# Moirai.net
KiCad netlist of a schematic drawn in EAGLE
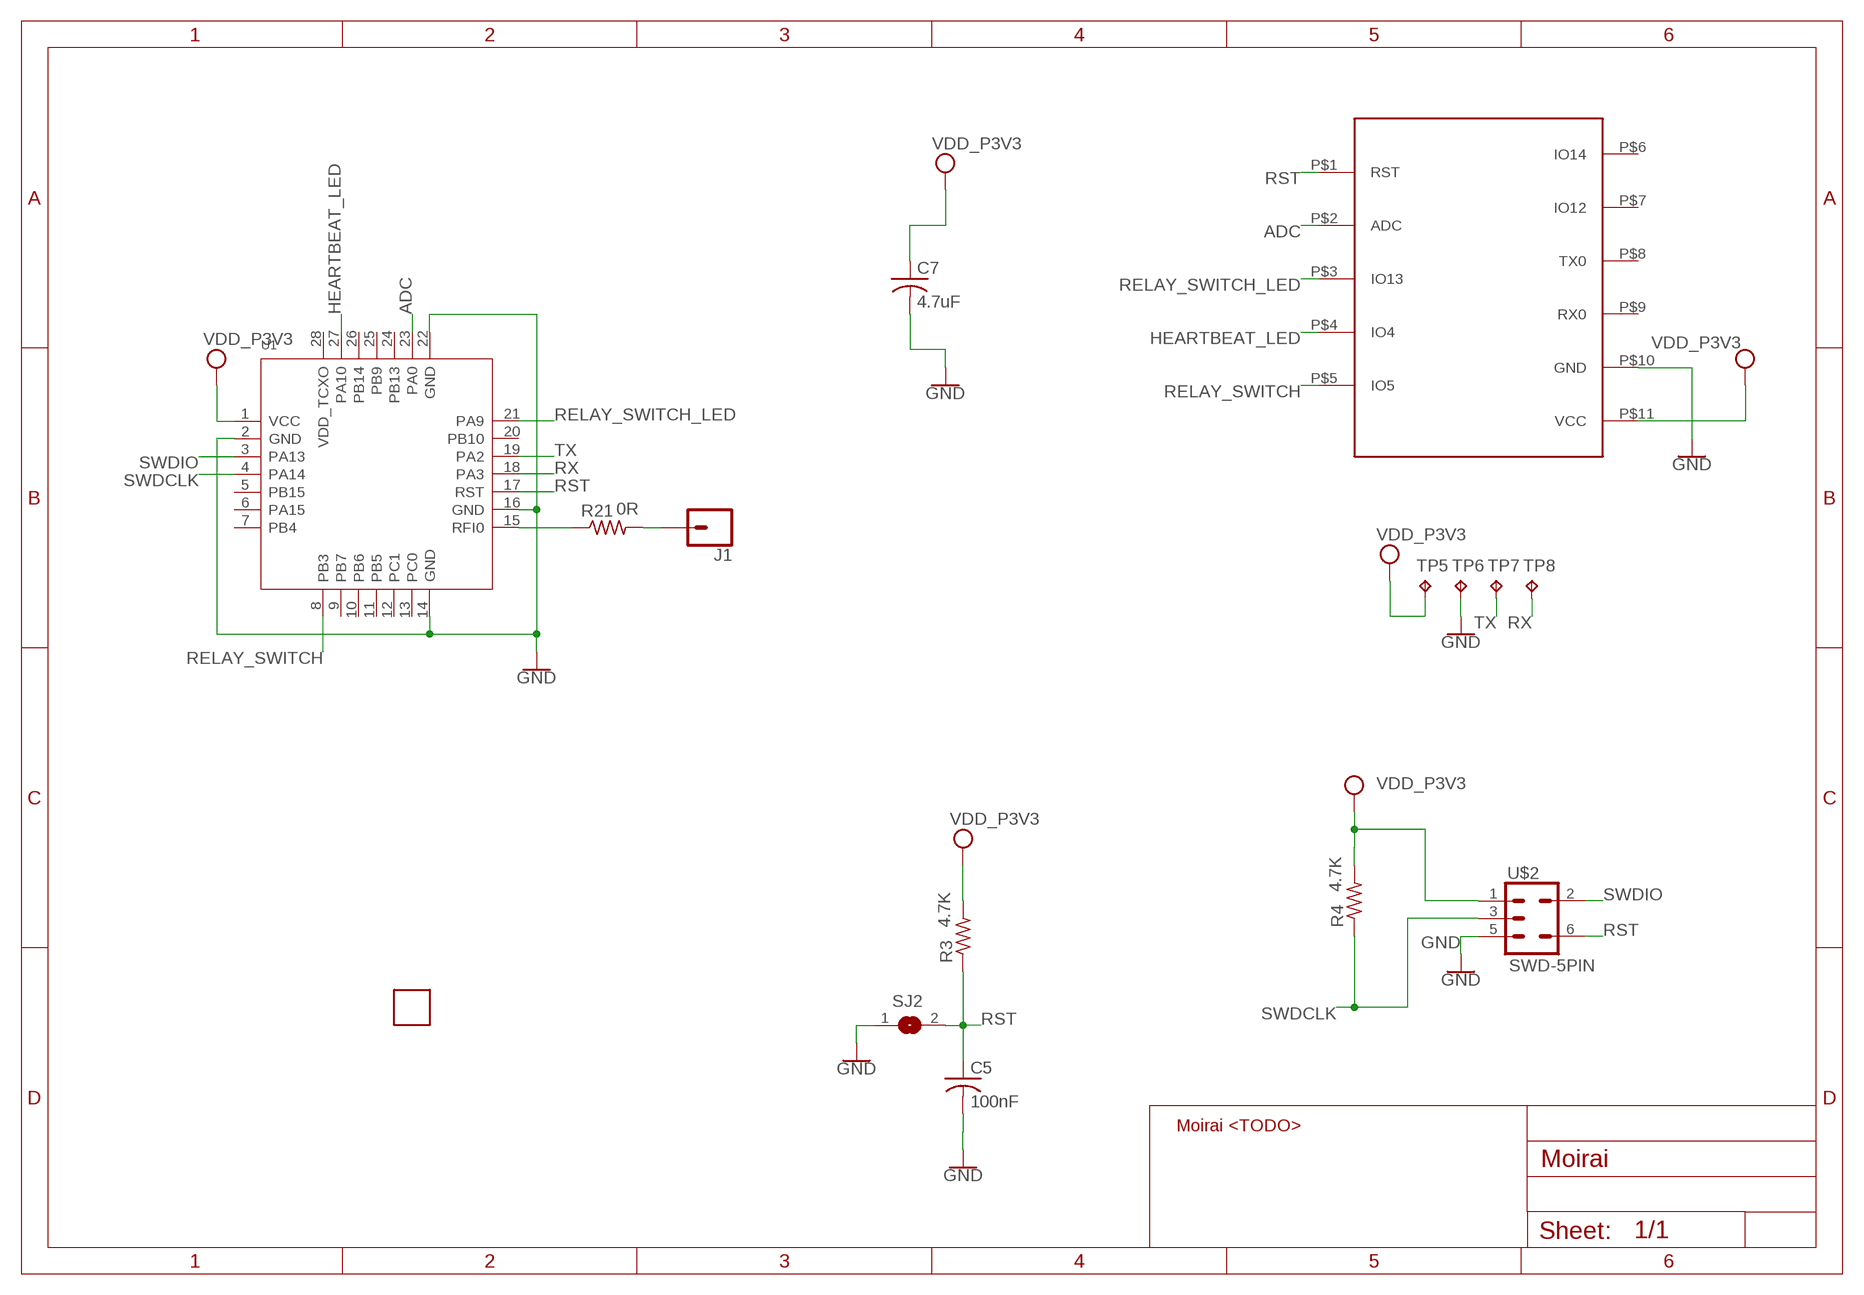
[diagram p0: schematic, sheet 1]

(export (version "E")
  (design (tool "Eeschema 10.0.6"))
  (components
    (comp (ref "C5")
      (value "100nF")
      (footprint "eagle-import:C0402")
      (libsource (lib "eagle-import") (part "C-USC0402"))
    )
    (comp (ref "C7")
      (value "4.7uF")
      (footprint "eagle-import:C0402")
      (libsource (lib "eagle-import") (part "C-USC0402"))
    )
    (comp (ref "J1")
      (value "CONN_01")
      (footprint "eagle-import:1X01")
      (libsource (lib "eagle-import") (part "CONN_01"))
    )
    (comp (ref "R3")
      (value "4.7K")
      (footprint "eagle-import:R0402")
      (libsource (lib "eagle-import") (part "R-US_R0402"))
    )
    (comp (ref "R4")
      (value "4.7K")
      (footprint "eagle-import:R0402")
      (libsource (lib "eagle-import") (part "R-US_R0402"))
    )
    (comp (ref "R21")
      (value "0R")
      (footprint "eagle-import:R0402")
      (libsource (lib "eagle-import") (part "R-US_R0402"))
    )
    (comp (ref "SJ2") (value "SJ") (footprint "eagle-import:SJ") (libsource (lib "eagle-import") (part "SJ")))
    (comp (ref "TP5")
      (value "TPB1,27")
      (footprint "eagle-import:B1,27")
      (libsource (lib "eagle-import") (part "TPB1,27"))
    )
    (comp (ref "TP6")
      (value "TPB1,27")
      (footprint "eagle-import:B1,27")
      (libsource (lib "eagle-import") (part "TPB1,27"))
    )
    (comp (ref "TP7")
      (value "TPB1,27")
      (footprint "eagle-import:B1,27")
      (libsource (lib "eagle-import") (part "TPB1,27"))
    )
    (comp (ref "TP8")
      (value "TPB1,27")
      (footprint "eagle-import:B1,27")
      (libsource (lib "eagle-import") (part "TPB1,27"))
    )
    (comp (ref "U$1")
      (value "ESP02SESP02S_MIRROR")
      (footprint "eagle-import:ESP02S_MIRROR")
      (libsource (lib "eagle-import") (part "ESP02SESP02S_MIRROR"))
    )
    (comp (ref "U$2")
      (value "SWD-5PIN")
      (footprint "eagle-import:PAD_05_03X2_TP_NO4")
      (libsource (lib "eagle-import") (part "SWD-5PIN"))
    )
    (comp (ref "U$3")
      (value "SMARTT_SMALL")
      (footprint "eagle-import:SMARTT_SMALL")
      (libsource (lib "eagle-import") (part "SMARTT_SMALL"))
    )
    (comp (ref "U1")
      (value "MODULE_LORA_E5")
      (footprint "eagle-import:MODULE28P-1.25-12X12X2.5MM")
      (libsource (lib "eagle-import") (part "MODULE_LORA_E5"))
    )
  )
  (nets
    (net (code "1") (name "/ADC") (class "Default")
      (node (ref "U$1") (pin "P$2") (pinfunction "ADC_P$2") (pintype "input"))
      (node (ref "U1") (pin "23") (pinfunction "PA0_23") (pintype "bidirectional"))
    )
    (net (code "2") (name "/HEARTBEAT_LED") (class "Default")
      (node (ref "U$1") (pin "P$4") (pinfunction "IO4_P$4") (pintype "bidirectional"))
      (node (ref "U1") (pin "27") (pinfunction "PA10_27") (pintype "bidirectional"))
    )
    (net (code "3") (name "/RELAY_SWITCH") (class "Default")
      (node (ref "U$1") (pin "P$5") (pinfunction "IO5_P$5") (pintype "bidirectional"))
      (node (ref "U1") (pin "8") (pinfunction "PB3_8") (pintype "bidirectional"))
    )
    (net (code "4") (name "/RELAY_SWITCH_LED") (class "Default")
      (node (ref "U$1") (pin "P$3") (pinfunction "IO13_P$3") (pintype "bidirectional"))
      (node (ref "U1") (pin "21") (pinfunction "PA9_21") (pintype "bidirectional"))
    )
    (net (code "5") (name "/RST") (class "Default")
      (node (ref "C5") (pin "1") (pinfunction "1_1") (pintype "passive"))
      (node (ref "R3") (pin "1") (pinfunction "1_1") (pintype "passive"))
      (node (ref "SJ2") (pin "2") (pinfunction "2_2") (pintype "passive"))
      (node (ref "U$1") (pin "P$1") (pinfunction "RST_P$1") (pintype "input"))
      (node (ref "U$2") (pin "6") (pinfunction "6_6") (pintype "bidirectional"))
      (node (ref "U1") (pin "17") (pinfunction "RST_17") (pintype "bidirectional"))
    )
    (net (code "6") (name "/RX") (class "Default")
      (node (ref "TP8") (pin "TP") (pinfunction "TP_TP") (pintype "input"))
      (node (ref "U1") (pin "18") (pinfunction "PA3_18") (pintype "bidirectional"))
    )
    (net (code "7") (name "/SWDCLK") (class "Default")
      (node (ref "R4") (pin "1") (pinfunction "1_1") (pintype "passive"))
      (node (ref "U$2") (pin "3") (pinfunction "3_3") (pintype "bidirectional"))
      (node (ref "U1") (pin "4") (pinfunction "PA14_4") (pintype "bidirectional"))
    )
    (net (code "8") (name "/SWDIO") (class "Default")
      (node (ref "U$2") (pin "2") (pinfunction "2_2") (pintype "bidirectional"))
      (node (ref "U1") (pin "3") (pinfunction "PA13_3") (pintype "bidirectional"))
    )
    (net (code "9") (name "/TX") (class "Default")
      (node (ref "TP7") (pin "TP") (pinfunction "TP_TP") (pintype "input"))
      (node (ref "U1") (pin "19") (pinfunction "PA2_19") (pintype "bidirectional"))
    )
    (net (code "10") (name "GND") (class "Default")
      (node (ref "C5") (pin "2") (pinfunction "2_2") (pintype "passive"))
      (node (ref "C7") (pin "2") (pinfunction "2_2") (pintype "passive"))
      (node (ref "SJ2") (pin "1") (pinfunction "1_1") (pintype "passive"))
      (node (ref "TP6") (pin "TP") (pinfunction "TP_TP") (pintype "input"))
      (node (ref "U$1") (pin "P$10") (pinfunction "GND_P$10") (pintype "power_in"))
      (node (ref "U$2") (pin "5") (pinfunction "5_5") (pintype "bidirectional"))
      (node (ref "U1") (pin "14") (pinfunction "GND_14") (pintype "bidirectional"))
      (node (ref "U1") (pin "16") (pinfunction "GND_16") (pintype "bidirectional"))
      (node (ref "U1") (pin "2") (pinfunction "GND_2") (pintype "bidirectional"))
      (node (ref "U1") (pin "22") (pinfunction "GND_22") (pintype "bidirectional"))
    )
    (net (code "11") (name "Net-(J1-Pad1)") (class "Default")
      (node (ref "J1") (pin "1") (pinfunction "1_1") (pintype "passive"))
      (node (ref "R21") (pin "2") (pinfunction "2_2") (pintype "passive"))
    )
    (net (code "12") (name "Net-(U1-RFI0)") (class "Default")
      (node (ref "R21") (pin "1") (pinfunction "1_1") (pintype "passive"))
      (node (ref "U1") (pin "15") (pinfunction "RFI0_15") (pintype "bidirectional"))
    )
    (net (code "13") (name "VDD_P3V3") (class "Default")
      (node (ref "C7") (pin "1") (pinfunction "1_1") (pintype "passive"))
      (node (ref "R3") (pin "2") (pinfunction "2_2") (pintype "passive"))
      (node (ref "R4") (pin "2") (pinfunction "2_2") (pintype "passive"))
      (node (ref "TP5") (pin "TP") (pinfunction "TP_TP") (pintype "input"))
      (node (ref "U$1") (pin "P$11") (pinfunction "VCC_P$11") (pintype "power_in"))
      (node (ref "U$2") (pin "1") (pinfunction "1_1") (pintype "bidirectional"))
      (node (ref "U1") (pin "1") (pinfunction "VCC_1") (pintype "bidirectional"))
    )
    (net (code "14") (name "unconnected-(U$1-IO12-PadP$7)") (class "Default")
      (node (ref "U$1") (pin "P$7") (pinfunction "IO12_P$7") (pintype "bidirectional"))
    )
    (net (code "15") (name "unconnected-(U$1-IO14-PadP$6)") (class "Default")
      (node (ref "U$1") (pin "P$6") (pinfunction "IO14_P$6") (pintype "bidirectional"))
    )
    (net (code "16") (name "unconnected-(U$1-RX0-PadP$9)") (class "Default")
      (node (ref "U$1") (pin "P$9") (pinfunction "RX0_P$9") (pintype "input"))
    )
    (net (code "17") (name "unconnected-(U$1-TX0-PadP$8)") (class "Default")
      (node (ref "U$1") (pin "P$8") (pinfunction "TX0_P$8") (pintype "output"))
    )
    (net (code "18") (name "unconnected-(U1-PA15-Pad6)") (class "Default")
      (node (ref "U1") (pin "6") (pinfunction "PA15_6") (pintype "bidirectional"))
    )
    (net (code "19") (name "unconnected-(U1-PB4-Pad7)") (class "Default")
      (node (ref "U1") (pin "7") (pinfunction "PB4_7") (pintype "bidirectional"))
    )
    (net (code "20") (name "unconnected-(U1-PB5-Pad11)") (class "Default")
      (node (ref "U1") (pin "11") (pinfunction "PB5_11") (pintype "bidirectional"))
    )
    (net (code "21") (name "unconnected-(U1-PB6-Pad10)") (class "Default")
      (node (ref "U1") (pin "10") (pinfunction "PB6_10") (pintype "bidirectional"))
    )
    (net (code "22") (name "unconnected-(U1-PB7-Pad9)") (class "Default")
      (node (ref "U1") (pin "9") (pinfunction "PB7_9") (pintype "bidirectional"))
    )
    (net (code "23") (name "unconnected-(U1-PB9-Pad25)") (class "Default")
      (node (ref "U1") (pin "25") (pinfunction "PB9_25") (pintype "bidirectional"))
    )
    (net (code "24") (name "unconnected-(U1-PB10-Pad20)") (class "Default")
      (node (ref "U1") (pin "20") (pinfunction "PB10_20") (pintype "bidirectional"))
    )
    (net (code "25") (name "unconnected-(U1-PB13-Pad24)") (class "Default")
      (node (ref "U1") (pin "24") (pinfunction "PB13_24") (pintype "bidirectional"))
    )
    (net (code "26") (name "unconnected-(U1-PB14-Pad26)") (class "Default")
      (node (ref "U1") (pin "26") (pinfunction "PB14_26") (pintype "bidirectional"))
    )
    (net (code "27") (name "unconnected-(U1-PB15-Pad5)") (class "Default")
      (node (ref "U1") (pin "5") (pinfunction "PB15_5") (pintype "bidirectional"))
    )
    (net (code "28") (name "unconnected-(U1-PC0-Pad13)") (class "Default")
      (node (ref "U1") (pin "13") (pinfunction "PC0_13") (pintype "bidirectional"))
    )
    (net (code "29") (name "unconnected-(U1-PC1-Pad12)") (class "Default")
      (node (ref "U1") (pin "12") (pinfunction "PC1_12") (pintype "bidirectional"))
    )
    (net (code "30") (name "unconnected-(U1-VDD_TCXO-Pad28)") (class "Default")
      (node (ref "U1") (pin "28") (pinfunction "VDD_TCXO_28") (pintype "bidirectional"))
    )
  )
)
